# scHnRk_7.net
KiCad netlist of a schematic drawn in EAGLE
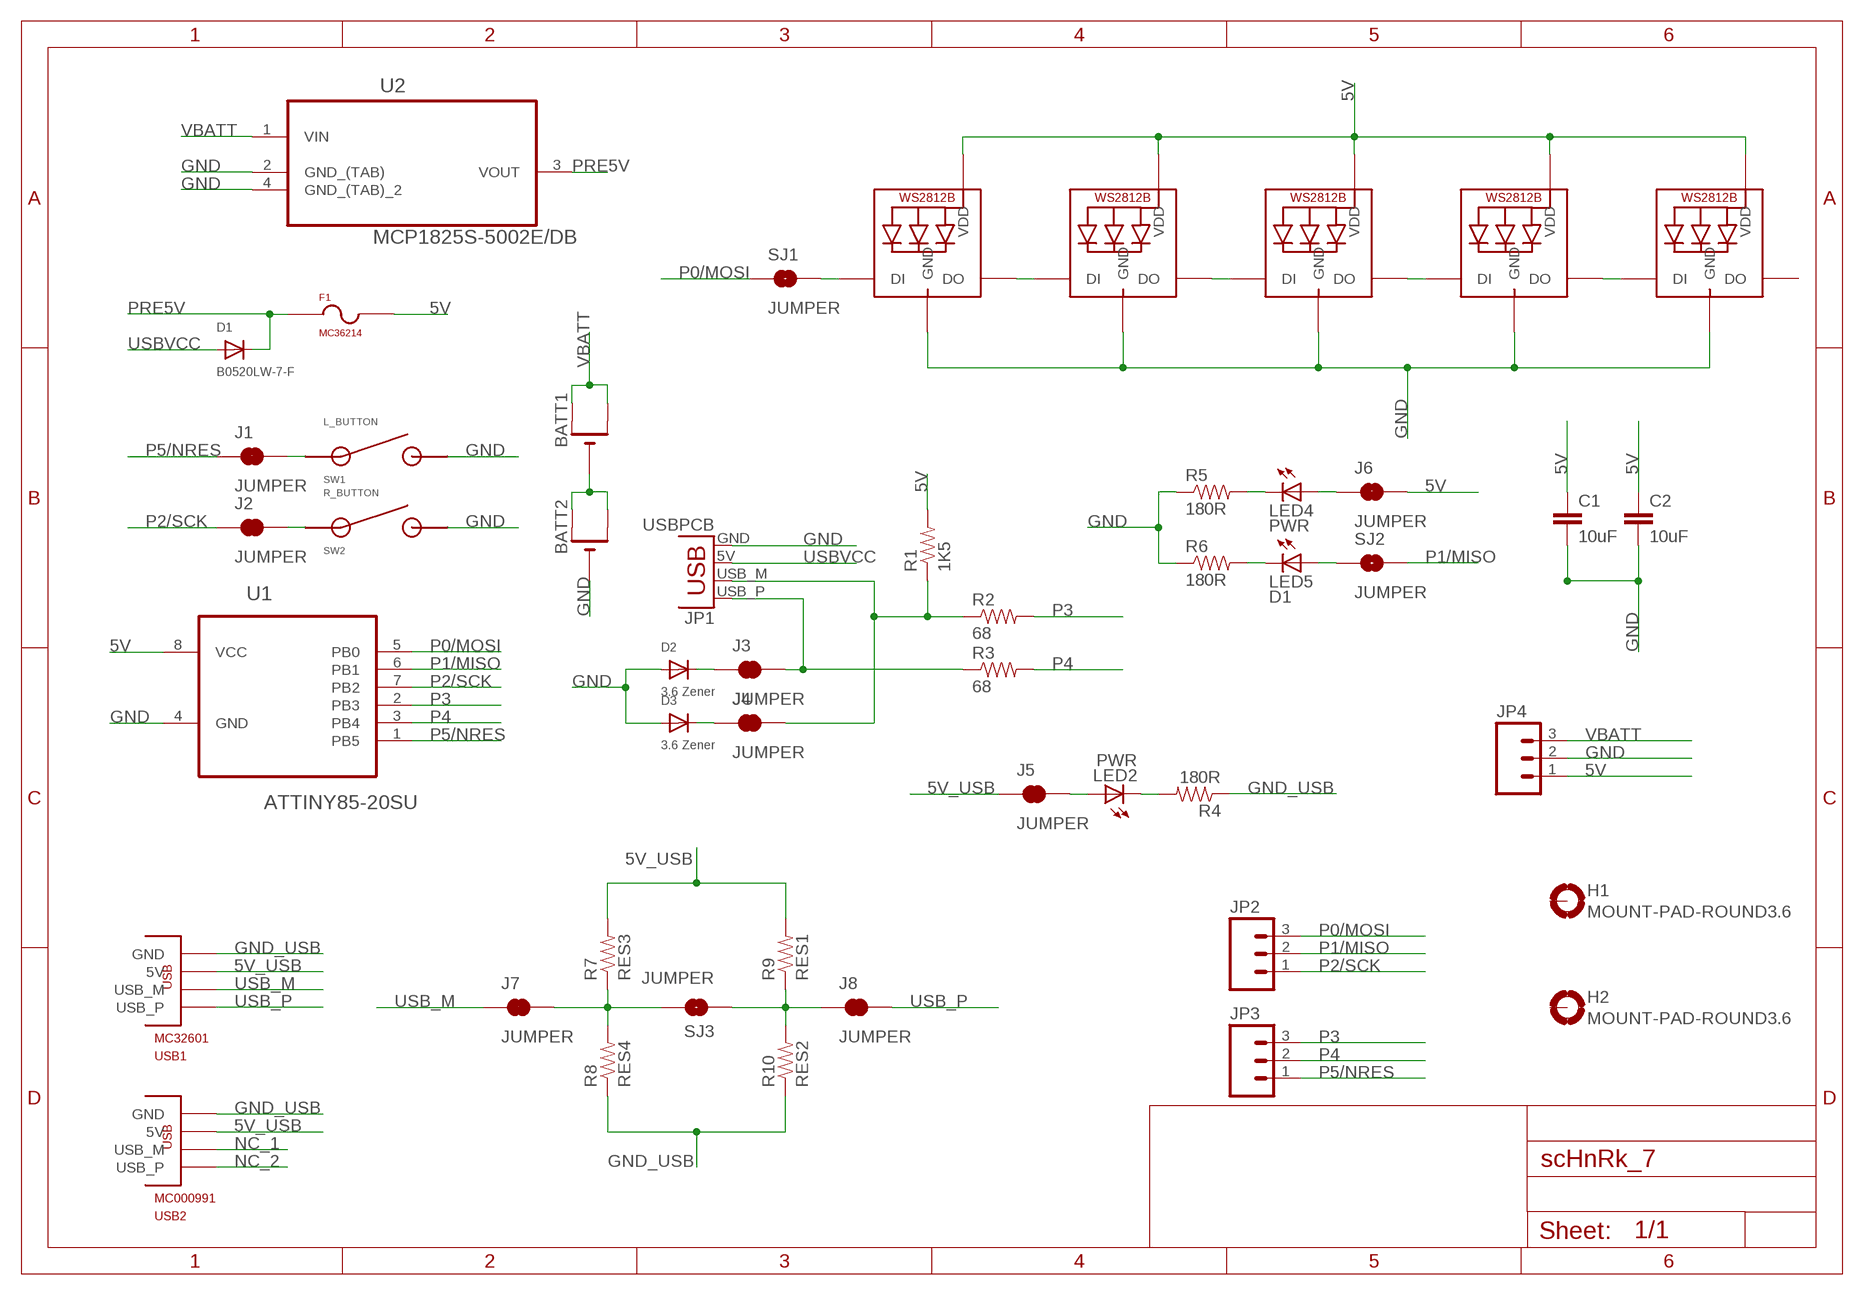
[diagram p0: schematic, sheet 1]

(export (version "E")
  (design (tool "Eeschema 10.0.6"))
  (components
    (comp (ref "BATT1")
      (value "CR2032SMT")
      (footprint "eagle-import:CR2032-SMD")
      (libsource (lib "eagle-import") (part "CR2032SMT"))
    )
    (comp (ref "BATT2")
      (value "CR2032SMT")
      (footprint "eagle-import:CR2032-SMD")
      (libsource (lib "eagle-import") (part "CR2032SMT"))
    )
    (comp (ref "C1")
      (value "10uF")
      (footprint "eagle-import:0805")
      (libsource (lib "eagle-import") (part "CAP0805"))
    )
    (comp (ref "C2")
      (value "10uF")
      (footprint "eagle-import:0805")
      (libsource (lib "eagle-import") (part "CAP0805"))
    )
    (comp (ref "D1")
      (value "B0520LW-7-F")
      (footprint "eagle-import:SOD-123")
      (libsource (lib "eagle-import") (part "DIODESOD-123"))
    )
    (comp (ref "D2")
      (value "3.6 Zener")
      (footprint "eagle-import:SOD-523")
      (libsource (lib "eagle-import") (part "DIODESOD-523"))
    )
    (comp (ref "D3")
      (value "3.6 Zener")
      (footprint "eagle-import:SOD-523")
      (libsource (lib "eagle-import") (part "DIODESOD-523"))
    )
    (comp (ref "F1")
      (value "MC36214")
      (footprint "eagle-import:MC36214")
      (libsource (lib "eagle-import") (part "MC36214"))
    )
    (comp (ref "H1")
      (value "MOUNT-PAD-ROUND3.6")
      (footprint "eagle-import:3,6-PAD")
      (libsource (lib "eagle-import") (part "MOUNT-PAD-ROUND3.6"))
    )
    (comp (ref "H2")
      (value "MOUNT-PAD-ROUND3.6")
      (footprint "eagle-import:3,6-PAD")
      (libsource (lib "eagle-import") (part "MOUNT-PAD-ROUND3.6"))
    )
    (comp (ref "J1")
      (value "JUMPER")
      (footprint "eagle-import:PAD-JUMPER-2-NC_BY_TRACE_YES_SILK")
      (libsource (lib "eagle-import") (part "JUMPER-PAD-2-NC_BY_TRACE"))
    )
    (comp (ref "J2")
      (value "JUMPER")
      (footprint "eagle-import:PAD-JUMPER-2-NC_BY_TRACE_YES_SILK")
      (libsource (lib "eagle-import") (part "JUMPER-PAD-2-NC_BY_TRACE"))
    )
    (comp (ref "J3")
      (value "JUMPER")
      (footprint "eagle-import:PAD-JUMPER-2-NC_BY_TRACE_YES_SILK")
      (libsource (lib "eagle-import") (part "JUMPER-PAD-2-NC_BY_TRACE"))
    )
    (comp (ref "J4")
      (value "JUMPER")
      (footprint "eagle-import:PAD-JUMPER-2-NC_BY_TRACE_YES_SILK")
      (libsource (lib "eagle-import") (part "JUMPER-PAD-2-NC_BY_TRACE"))
    )
    (comp (ref "J5")
      (value "JUMPER")
      (footprint "eagle-import:PAD-JUMPER-2-NC_BY_TRACE_YES_SILK")
      (libsource (lib "eagle-import") (part "JUMPER-PAD-2-NC_BY_TRACE"))
    )
    (comp (ref "J6")
      (value "JUMPER")
      (footprint "eagle-import:PAD-JUMPER-2-NC_BY_TRACE_YES_SILK")
      (libsource (lib "eagle-import") (part "JUMPER-PAD-2-NC_BY_TRACE"))
    )
    (comp (ref "J7")
      (value "JUMPER")
      (footprint "eagle-import:PAD-JUMPER-2-NC_BY_TRACE_YES_SILK")
      (libsource (lib "eagle-import") (part "JUMPER-PAD-2-NC_BY_TRACE"))
    )
    (comp (ref "J8")
      (value "JUMPER")
      (footprint "eagle-import:PAD-JUMPER-2-NC_BY_TRACE_YES_SILK")
      (libsource (lib "eagle-import") (part "JUMPER-PAD-2-NC_BY_TRACE"))
    )
    (comp (ref "JP1")
      (value "USBPCB")
      (footprint "eagle-import:USB-A-PCB")
      (libsource (lib "eagle-import") (part "USBPCB"))
    )
    (comp (ref "JP2")
      (value "M031X03_NO_SILK")
      (footprint "eagle-import:1X03_NO_SILK")
      (libsource (lib "eagle-import") (part "M031X03_NO_SILK"))
    )
    (comp (ref "JP3")
      (value "M031X03_NO_SILK")
      (footprint "eagle-import:1X03_NO_SILK")
      (libsource (lib "eagle-import") (part "M031X03_NO_SILK"))
    )
    (comp (ref "JP4")
      (value "M031X03_NO_SILK")
      (footprint "eagle-import:1X03_NO_SILK")
      (libsource (lib "eagle-import") (part "M031X03_NO_SILK"))
    )
    (comp (ref "LED1")
      (value "WS2812B5050")
      (footprint "eagle-import:WS2812B")
      (libsource (lib "eagle-import") (part "WS2812B5050"))
    )
    (comp (ref "LED2")
      (value "PWR")
      (footprint "eagle-import:CHIPLED_0603")
      (libsource (lib "eagle-import") (part "LEDCHIPLED_0603"))
    )
    (comp (ref "LED3")
      (value "WS2812B5050")
      (footprint "eagle-import:WS2812B")
      (libsource (lib "eagle-import") (part "WS2812B5050"))
    )
    (comp (ref "LED4")
      (value "PWR")
      (footprint "eagle-import:CHIPLED_0603")
      (libsource (lib "eagle-import") (part "LEDCHIPLED_0603"))
    )
    (comp (ref "LED5")
      (value "D1")
      (footprint "eagle-import:CHIPLED_0603")
      (libsource (lib "eagle-import") (part "LEDCHIPLED_0603"))
    )
    (comp (ref "LED6")
      (value "WS2812B5050")
      (footprint "eagle-import:WS2812B")
      (libsource (lib "eagle-import") (part "WS2812B5050"))
    )
    (comp (ref "LED7")
      (value "WS2812B5050")
      (footprint "eagle-import:WS2812B")
      (libsource (lib "eagle-import") (part "WS2812B5050"))
    )
    (comp (ref "LED8")
      (value "WS2812B5050")
      (footprint "eagle-import:WS2812B")
      (libsource (lib "eagle-import") (part "WS2812B5050"))
    )
    (comp (ref "R1")
      (value "1K5")
      (footprint "eagle-import:0805")
      (libsource (lib "eagle-import") (part "RESISTOR0805-RES"))
    )
    (comp (ref "R2")
      (value "68")
      (footprint "eagle-import:0805")
      (libsource (lib "eagle-import") (part "RESISTOR0805-RES"))
    )
    (comp (ref "R3")
      (value "68")
      (footprint "eagle-import:0805")
      (libsource (lib "eagle-import") (part "RESISTOR0805-RES"))
    )
    (comp (ref "R4")
      (value "180R")
      (footprint "eagle-import:0805")
      (libsource (lib "eagle-import") (part "RESISTOR0805-RES"))
    )
    (comp (ref "R5")
      (value "180R")
      (footprint "eagle-import:0805")
      (libsource (lib "eagle-import") (part "RESISTOR0805-RES"))
    )
    (comp (ref "R6")
      (value "180R")
      (footprint "eagle-import:0805")
      (libsource (lib "eagle-import") (part "RESISTOR0805-RES"))
    )
    (comp (ref "R7")
      (value "RES3")
      (footprint "eagle-import:0805")
      (libsource (lib "eagle-import") (part "RESISTOR0805-RES"))
    )
    (comp (ref "R8")
      (value "RES4")
      (footprint "eagle-import:0805")
      (libsource (lib "eagle-import") (part "RESISTOR0805-RES"))
    )
    (comp (ref "R9")
      (value "RES1")
      (footprint "eagle-import:0805")
      (libsource (lib "eagle-import") (part "RESISTOR0805-RES"))
    )
    (comp (ref "R10")
      (value "RES2")
      (footprint "eagle-import:0805")
      (libsource (lib "eagle-import") (part "RESISTOR0805-RES"))
    )
    (comp (ref "SJ1")
      (value "JUMPER")
      (footprint "eagle-import:PAD-JUMPER-2-NO_YES_SILK")
      (libsource (lib "eagle-import") (part "JUMPER-PAD-2-NOYES_SILK"))
    )
    (comp (ref "SJ2")
      (value "JUMPER")
      (footprint "eagle-import:PAD-JUMPER-2-NO_YES_SILK")
      (libsource (lib "eagle-import") (part "JUMPER-PAD-2-NOYES_SILK"))
    )
    (comp (ref "SJ3")
      (value "JUMPER")
      (footprint "eagle-import:PAD-JUMPER-2-NO_YES_SILK")
      (libsource (lib "eagle-import") (part "JUMPER-PAD-2-NOYES_SILK"))
    )
    (comp (ref "SW1")
      (value "L_BUTTON")
      (footprint "eagle-import:SKRBAGE010")
      (libsource (lib "eagle-import") (part "SKRBAGE010"))
    )
    (comp (ref "SW2")
      (value "R_BUTTON")
      (footprint "eagle-import:SKRBAGE010")
      (libsource (lib "eagle-import") (part "SKRBAGE010"))
    )
    (comp (ref "U1")
      (value "ATTINY85-20SU")
      (footprint "eagle-import:SOIC127P798X216-8N")
      (libsource (lib "eagle-import") (part "ATTINY85-20SU"))
    )
    (comp (ref "U2")
      (value "MCP1825S-5002E/DB")
      (footprint "eagle-import:SOT230P700X180-4N")
      (libsource (lib "eagle-import") (part "MCP1825S-5002E/DB"))
    )
    (comp (ref "USB1")
      (value "MC32601")
      (footprint "eagle-import:MC32601")
      (libsource (lib "eagle-import") (part "MC32601"))
    )
    (comp (ref "USB2")
      (value "MC000991")
      (footprint "eagle-import:MC000991")
      (libsource (lib "eagle-import") (part "MC000991"))
    )
  )
  (nets
    (net (code "1") (name "/5V") (class "Default")
      (node (ref "C1") (pin "1") (pinfunction "1_1") (pintype "passive"))
      (node (ref "C2") (pin "1") (pinfunction "1_1") (pintype "passive"))
      (node (ref "F1") (pin "P$2") (pinfunction "P$2_P$2") (pintype "bidirectional"))
      (node (ref "J6") (pin "2") (pinfunction "2_2") (pintype "passive"))
      (node (ref "JP4") (pin "1") (pinfunction "1_1") (pintype "passive"))
      (node (ref "LED1") (pin "1-VDD") (pinfunction "VDD_1-VDD") (pintype "power_in"))
      (node (ref "LED3") (pin "1-VDD") (pinfunction "VDD_1-VDD") (pintype "power_in"))
      (node (ref "LED6") (pin "1-VDD") (pinfunction "VDD_1-VDD") (pintype "power_in"))
      (node (ref "LED7") (pin "1-VDD") (pinfunction "VDD_1-VDD") (pintype "power_in"))
      (node (ref "LED8") (pin "1-VDD") (pinfunction "VDD_1-VDD") (pintype "power_in"))
      (node (ref "R1") (pin "2") (pinfunction "2_2") (pintype "passive"))
      (node (ref "U1") (pin "8") (pinfunction "VCC_8") (pintype "power_in"))
    )
    (net (code "2") (name "/5V_USB") (class "Default")
      (node (ref "J5") (pin "1") (pinfunction "1_1") (pintype "passive"))
      (node (ref "R7") (pin "2") (pinfunction "2_2") (pintype "passive"))
      (node (ref "R9") (pin "2") (pinfunction "2_2") (pintype "passive"))
      (node (ref "USB1") (pin "P$2") (pinfunction "5V_P$2") (pintype "bidirectional"))
      (node (ref "USB2") (pin "P$4") (pinfunction "5V_P$4") (pintype "bidirectional"))
    )
    (net (code "3") (name "/GND") (class "Default")
      (node (ref "BATT2") (pin "-") (pinfunction "-_-") (pintype "passive"))
      (node (ref "C1") (pin "2") (pinfunction "2_2") (pintype "passive"))
      (node (ref "C2") (pin "2") (pinfunction "2_2") (pintype "passive"))
      (node (ref "D2") (pin "A") (pinfunction "A_A") (pintype "passive"))
      (node (ref "D3") (pin "A") (pinfunction "A_A") (pintype "passive"))
      (node (ref "JP1") (pin "GND") (pinfunction "GND_GND") (pintype "bidirectional"))
      (node (ref "JP4") (pin "2") (pinfunction "2_2") (pintype "passive"))
      (node (ref "LED1") (pin "3-GND") (pinfunction "GND_3-GND") (pintype "power_in"))
      (node (ref "LED3") (pin "3-GND") (pinfunction "GND_3-GND") (pintype "power_in"))
      (node (ref "LED6") (pin "3-GND") (pinfunction "GND_3-GND") (pintype "power_in"))
      (node (ref "LED7") (pin "3-GND") (pinfunction "GND_3-GND") (pintype "power_in"))
      (node (ref "LED8") (pin "3-GND") (pinfunction "GND_3-GND") (pintype "power_in"))
      (node (ref "R5") (pin "1") (pinfunction "1_1") (pintype "passive"))
      (node (ref "R6") (pin "1") (pinfunction "1_1") (pintype "passive"))
      (node (ref "SW1") (pin "P$2") (pinfunction "P$2_P$2") (pintype "bidirectional"))
      (node (ref "SW1") (pin "P$4") (pinfunction "P$2_P$4") (pintype "bidirectional"))
      (node (ref "SW2") (pin "P$2") (pinfunction "P$2_P$2") (pintype "bidirectional"))
      (node (ref "SW2") (pin "P$4") (pinfunction "P$2_P$4") (pintype "bidirectional"))
      (node (ref "U1") (pin "4") (pinfunction "GND_4") (pintype "passive"))
      (node (ref "U2") (pin "2") (pinfunction "GND_(TAB)_2") (pintype "passive"))
      (node (ref "U2") (pin "4") (pinfunction "GND_(TAB)_2_4") (pintype "passive"))
    )
    (net (code "4") (name "/GND_USB") (class "Default")
      (node (ref "R10") (pin "1") (pinfunction "1_1") (pintype "passive"))
      (node (ref "R4") (pin "1") (pinfunction "1_1") (pintype "passive"))
      (node (ref "R8") (pin "1") (pinfunction "1_1") (pintype "passive"))
      (node (ref "USB1") (pin "P$5") (pinfunction "GND_P$5") (pintype "bidirectional"))
      (node (ref "USB2") (pin "P$1") (pinfunction "GND_P$1") (pintype "bidirectional"))
    )
    (net (code "5") (name "/NC_1") (class "Default")
      (node (ref "USB2") (pin "P$3") (pinfunction "USB_M_P$3") (pintype "bidirectional"))
    )
    (net (code "6") (name "/NC_2") (class "Default")
      (node (ref "USB2") (pin "P$2") (pinfunction "USB_P_P$2") (pintype "bidirectional"))
    )
    (net (code "7") (name "/P0{slash}MOSI") (class "Default")
      (node (ref "JP2") (pin "3") (pinfunction "3_3") (pintype "passive"))
      (node (ref "SJ1") (pin "1") (pinfunction "1_1") (pintype "passive"))
      (node (ref "U1") (pin "5") (pinfunction "PB0_5") (pintype "bidirectional"))
    )
    (net (code "8") (name "/P1{slash}MISO") (class "Default")
      (node (ref "JP2") (pin "2") (pinfunction "2_2") (pintype "passive"))
      (node (ref "SJ2") (pin "2") (pinfunction "2_2") (pintype "passive"))
      (node (ref "U1") (pin "6") (pinfunction "PB1_6") (pintype "bidirectional"))
    )
    (net (code "9") (name "/P2{slash}SCK") (class "Default")
      (node (ref "J2") (pin "1") (pinfunction "1_1") (pintype "passive"))
      (node (ref "JP2") (pin "1") (pinfunction "1_1") (pintype "passive"))
      (node (ref "U1") (pin "7") (pinfunction "PB2_7") (pintype "bidirectional"))
    )
    (net (code "10") (name "/P3") (class "Default")
      (node (ref "JP3") (pin "3") (pinfunction "3_3") (pintype "passive"))
      (node (ref "R2") (pin "2") (pinfunction "2_2") (pintype "passive"))
      (node (ref "U1") (pin "2") (pinfunction "PB3_2") (pintype "bidirectional"))
    )
    (net (code "11") (name "/P4") (class "Default")
      (node (ref "JP3") (pin "2") (pinfunction "2_2") (pintype "passive"))
      (node (ref "R3") (pin "2") (pinfunction "2_2") (pintype "passive"))
      (node (ref "U1") (pin "3") (pinfunction "PB4_3") (pintype "bidirectional"))
    )
    (net (code "12") (name "/P5{slash}NRES") (class "Default")
      (node (ref "J1") (pin "1") (pinfunction "1_1") (pintype "passive"))
      (node (ref "JP3") (pin "1") (pinfunction "1_1") (pintype "passive"))
      (node (ref "U1") (pin "1") (pinfunction "PB5_1") (pintype "bidirectional"))
    )
    (net (code "13") (name "/PRE5V") (class "Default")
      (node (ref "D1") (pin "C") (pinfunction "C_C") (pintype "passive"))
      (node (ref "F1") (pin "P$1") (pinfunction "P$1_P$1") (pintype "bidirectional"))
      (node (ref "U2") (pin "3") (pinfunction "VOUT_3") (pintype "output"))
    )
    (net (code "14") (name "/USBVCC") (class "Default")
      (node (ref "D1") (pin "A") (pinfunction "A_A") (pintype "passive"))
      (node (ref "JP1") (pin "5V") (pinfunction "VBUS_5V") (pintype "bidirectional"))
    )
    (net (code "15") (name "/USB_M") (class "Default")
      (node (ref "J7") (pin "1") (pinfunction "1_1") (pintype "passive"))
      (node (ref "USB1") (pin "P$3") (pinfunction "USB_M_P$3") (pintype "bidirectional"))
    )
    (net (code "16") (name "/USB_P") (class "Default")
      (node (ref "J8") (pin "2") (pinfunction "2_2") (pintype "passive"))
      (node (ref "USB1") (pin "P$4") (pinfunction "USB_P_P$4") (pintype "bidirectional"))
    )
    (net (code "17") (name "/VBATT") (class "Default")
      (node (ref "BATT1") (pin "+$1") (pinfunction "+_+$1") (pintype "passive"))
      (node (ref "BATT1") (pin "+$2") (pinfunction "+1_+$2") (pintype "passive"))
      (node (ref "JP4") (pin "3") (pinfunction "3_3") (pintype "passive"))
      (node (ref "U2") (pin "1") (pinfunction "VIN_1") (pintype "input"))
    )
    (net (code "18") (name "Net-(BATT2-+)") (class "Default")
      (node (ref "BATT1") (pin "-") (pinfunction "-_-") (pintype "passive"))
      (node (ref "BATT2") (pin "+$1") (pinfunction "+_+$1") (pintype "passive"))
      (node (ref "BATT2") (pin "+$2") (pinfunction "+1_+$2") (pintype "passive"))
    )
    (net (code "19") (name "Net-(D2-C)") (class "Default")
      (node (ref "D2") (pin "K") (pinfunction "C_K") (pintype "passive"))
      (node (ref "J3") (pin "1") (pinfunction "1_1") (pintype "passive"))
    )
    (net (code "20") (name "Net-(D3-C)") (class "Default")
      (node (ref "D3") (pin "K") (pinfunction "C_K") (pintype "passive"))
      (node (ref "J4") (pin "1") (pinfunction "1_1") (pintype "passive"))
    )
    (net (code "21") (name "Net-(J1-Pad2)") (class "Default")
      (node (ref "J1") (pin "2") (pinfunction "2_2") (pintype "passive"))
      (node (ref "SW1") (pin "P$1") (pinfunction "P$1_P$1") (pintype "bidirectional"))
      (node (ref "SW1") (pin "P$3") (pinfunction "P$1_P$3") (pintype "bidirectional"))
    )
    (net (code "22") (name "Net-(J2-Pad2)") (class "Default")
      (node (ref "J2") (pin "2") (pinfunction "2_2") (pintype "passive"))
      (node (ref "SW2") (pin "P$1") (pinfunction "P$1_P$1") (pintype "bidirectional"))
      (node (ref "SW2") (pin "P$3") (pinfunction "P$1_P$3") (pintype "bidirectional"))
    )
    (net (code "23") (name "Net-(J5-Pad2)") (class "Default")
      (node (ref "J5") (pin "2") (pinfunction "2_2") (pintype "passive"))
      (node (ref "LED2") (pin "A") (pinfunction "A_A") (pintype "passive"))
    )
    (net (code "24") (name "Net-(J6-Pad1)") (class "Default")
      (node (ref "J6") (pin "1") (pinfunction "1_1") (pintype "passive"))
      (node (ref "LED4") (pin "A") (pinfunction "A_A") (pintype "passive"))
    )
    (net (code "25") (name "Net-(J7-Pad2)") (class "Default")
      (node (ref "J7") (pin "2") (pinfunction "2_2") (pintype "passive"))
      (node (ref "R7") (pin "1") (pinfunction "1_1") (pintype "passive"))
      (node (ref "R8") (pin "2") (pinfunction "2_2") (pintype "passive"))
      (node (ref "SJ3") (pin "2") (pinfunction "2_2") (pintype "passive"))
    )
    (net (code "26") (name "Net-(J8-Pad1)") (class "Default")
      (node (ref "J8") (pin "1") (pinfunction "1_1") (pintype "passive"))
      (node (ref "R10") (pin "2") (pinfunction "2_2") (pintype "passive"))
      (node (ref "R9") (pin "1") (pinfunction "1_1") (pintype "passive"))
      (node (ref "SJ3") (pin "1") (pinfunction "1_1") (pintype "passive"))
    )
    (net (code "27") (name "Net-(JP1-D+)") (class "Default")
      (node (ref "J3") (pin "2") (pinfunction "2_2") (pintype "passive"))
      (node (ref "JP1") (pin "USB_P") (pinfunction "D+_USB_P") (pintype "bidirectional"))
      (node (ref "R3") (pin "1") (pinfunction "1_1") (pintype "passive"))
    )
    (net (code "28") (name "Net-(JP1-D-)") (class "Default")
      (node (ref "J4") (pin "2") (pinfunction "2_2") (pintype "passive"))
      (node (ref "JP1") (pin "USB_M") (pinfunction "D-_USB_M") (pintype "bidirectional"))
      (node (ref "R1") (pin "1") (pinfunction "1_1") (pintype "passive"))
      (node (ref "R2") (pin "1") (pinfunction "1_1") (pintype "passive"))
    )
    (net (code "29") (name "Net-(LED1-DI)") (class "Default")
      (node (ref "LED1") (pin "4-DIN") (pinfunction "DI_4-DIN") (pintype "input"))
      (node (ref "SJ1") (pin "2") (pinfunction "2_2") (pintype "passive"))
    )
    (net (code "30") (name "Net-(LED1-DO)") (class "Default")
      (node (ref "LED1") (pin "2-DOUT") (pinfunction "DO_2-DOUT") (pintype "output"))
      (node (ref "LED3") (pin "4-DIN") (pinfunction "DI_4-DIN") (pintype "input"))
    )
    (net (code "31") (name "Net-(LED2-PadC)") (class "Default")
      (node (ref "LED2") (pin "C") (pinfunction "C_C") (pintype "passive"))
      (node (ref "R4") (pin "2") (pinfunction "2_2") (pintype "passive"))
    )
    (net (code "32") (name "Net-(LED3-DO)") (class "Default")
      (node (ref "LED3") (pin "2-DOUT") (pinfunction "DO_2-DOUT") (pintype "output"))
      (node (ref "LED6") (pin "4-DIN") (pinfunction "DI_4-DIN") (pintype "input"))
    )
    (net (code "33") (name "Net-(LED4-PadC)") (class "Default")
      (node (ref "LED4") (pin "C") (pinfunction "C_C") (pintype "passive"))
      (node (ref "R5") (pin "2") (pinfunction "2_2") (pintype "passive"))
    )
    (net (code "34") (name "Net-(LED5-PadA)") (class "Default")
      (node (ref "LED5") (pin "A") (pinfunction "A_A") (pintype "passive"))
      (node (ref "SJ2") (pin "1") (pinfunction "1_1") (pintype "passive"))
    )
    (net (code "35") (name "Net-(LED5-PadC)") (class "Default")
      (node (ref "LED5") (pin "C") (pinfunction "C_C") (pintype "passive"))
      (node (ref "R6") (pin "2") (pinfunction "2_2") (pintype "passive"))
    )
    (net (code "36") (name "Net-(LED6-DO)") (class "Default")
      (node (ref "LED6") (pin "2-DOUT") (pinfunction "DO_2-DOUT") (pintype "output"))
      (node (ref "LED7") (pin "4-DIN") (pinfunction "DI_4-DIN") (pintype "input"))
    )
    (net (code "37") (name "Net-(LED7-DO)") (class "Default")
      (node (ref "LED7") (pin "2-DOUT") (pinfunction "DO_2-DOUT") (pintype "output"))
      (node (ref "LED8") (pin "4-DIN") (pinfunction "DI_4-DIN") (pintype "input"))
    )
    (net (code "38") (name "unconnected-(H1-MOUNT-PadB3,6)") (class "Default")
      (node (ref "H1") (pin "B3,6") (pinfunction "MOUNT_B3,6") (pintype "passive"))
    )
    (net (code "39") (name "unconnected-(H2-MOUNT-PadB3,6)") (class "Default")
      (node (ref "H2") (pin "B3,6") (pinfunction "MOUNT_B3,6") (pintype "passive"))
    )
    (net (code "40") (name "unconnected-(LED8-DO-Pad2-DOUT)") (class "Default")
      (node (ref "LED8") (pin "2-DOUT") (pinfunction "DO_2-DOUT") (pintype "output"))
    )
  )
)
